# M_H_ext_sound.net
KiCad netlist of a schematic drawn in EAGLE
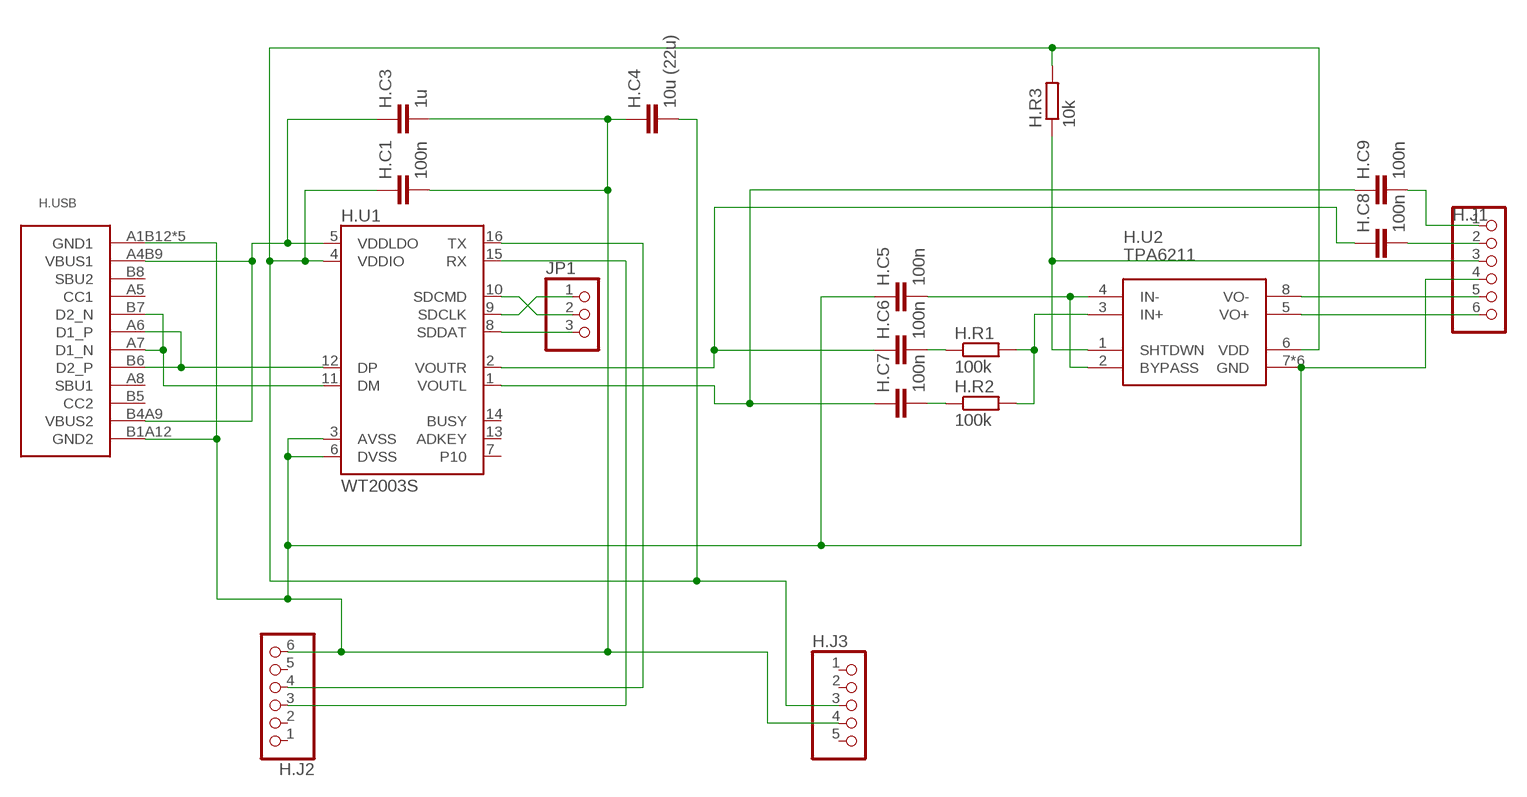
[diagram p0: schematic, sheet 1]

(export (version "E")
  (design (tool "Eeschema 10.0.6"))
  (components
    (comp (ref "H.C1")
      (value "100n")
      (footprint "eagle-import:C0603")
      (libsource (lib "eagle-import") (part "C-EUC0603"))
    )
    (comp (ref "H.C3")
      (value "1u")
      (footprint "eagle-import:C0603")
      (libsource (lib "eagle-import") (part "C-EUC0603"))
    )
    (comp (ref "H.C4")
      (value "10u (22u)")
      (footprint "eagle-import:C0805")
      (libsource (lib "eagle-import") (part "C-EUC0805"))
    )
    (comp (ref "H.C5")
      (value "100n")
      (footprint "eagle-import:C0603")
      (libsource (lib "eagle-import") (part "C-EUC0603"))
    )
    (comp (ref "H.C6")
      (value "100n")
      (footprint "eagle-import:C0603")
      (libsource (lib "eagle-import") (part "C-EUC0603"))
    )
    (comp (ref "H.C7")
      (value "100n")
      (footprint "eagle-import:C0603")
      (libsource (lib "eagle-import") (part "C-EUC0603"))
    )
    (comp (ref "H.C8")
      (value "100n")
      (footprint "eagle-import:C0603")
      (libsource (lib "eagle-import") (part "C-EUC0603"))
    )
    (comp (ref "H.C9")
      (value "100n")
      (footprint "eagle-import:C0603")
      (libsource (lib "eagle-import") (part "C-EUC0603"))
    )
    (comp (ref "H.J1")
      (value "PINHD-1X6")
      (footprint "eagle-import:1X06")
      (libsource (lib "eagle-import") (part "PINHD-1X6"))
    )
    (comp (ref "H.J2")
      (value "PINHD-1X6")
      (footprint "eagle-import:1X06")
      (libsource (lib "eagle-import") (part "PINHD-1X6"))
    )
    (comp (ref "H.J3")
      (value "PINHD-1X5")
      (footprint "eagle-import:1X05")
      (libsource (lib "eagle-import") (part "PINHD-1X5"))
    )
    (comp (ref "H.R1")
      (value "100k")
      (footprint "eagle-import:R0603")
      (libsource (lib "eagle-import") (part "R-EU_R0603"))
    )
    (comp (ref "H.R2")
      (value "100k")
      (footprint "eagle-import:R0603")
      (libsource (lib "eagle-import") (part "R-EU_R0603"))
    )
    (comp (ref "H.R3")
      (value "10k")
      (footprint "eagle-import:R0603")
      (libsource (lib "eagle-import") (part "R-EU_R0603"))
    )
    (comp (ref "H.U1")
      (value "WT2003S")
      (footprint "eagle-import:SO16")
      (libsource (lib "eagle-import") (part "WT2003S"))
    )
    (comp (ref "H.U2")
      (value "TPA6211")
      (footprint "eagle-import:MSOP-POWERPAD-8")
      (libsource (lib "eagle-import") (part "TPA6211"))
    )
    (comp (ref "H.USB")
      (value "USB-C")
      (footprint "eagle-import:USB-C")
      (libsource (lib "eagle-import") (part "USB-C"))
    )
    (comp (ref "JP1")
      (value "PINHD-1X3")
      (footprint "eagle-import:1X03")
      (libsource (lib "eagle-import") (part "PINHD-1X3"))
    )
  )
  (nets
    (net (code "1") (name "Net-(H.C6-Pad2)") (class "Default")
      (node (ref "H.C6") (pin "2") (pinfunction "2_2") (pintype "passive"))
      (node (ref "H.R1") (pin "1") (pinfunction "1_1") (pintype "passive"))
    )
    (net (code "2") (name "Net-(H.C7-Pad2)") (class "Default")
      (node (ref "H.C7") (pin "2") (pinfunction "2_2") (pintype "passive"))
      (node (ref "H.R2") (pin "1") (pinfunction "1_1") (pintype "passive"))
    )
    (net (code "3") (name "Net-(H.C8-Pad2)") (class "Default")
      (node (ref "H.C8") (pin "2") (pinfunction "2_2") (pintype "passive"))
      (node (ref "H.J1") (pin "2") (pinfunction "2_2") (pintype "passive"))
    )
    (net (code "4") (name "Net-(H.C9-Pad2)") (class "Default")
      (node (ref "H.C9") (pin "2") (pinfunction "2_2") (pintype "passive"))
      (node (ref "H.J1") (pin "1") (pinfunction "1_1") (pintype "passive"))
    )
    (net (code "5") (name "Net-(H.U1-AVSS)") (class "Default")
      (node (ref "H.C1") (pin "2") (pinfunction "2_2") (pintype "passive"))
      (node (ref "H.C3") (pin "2") (pinfunction "2_2") (pintype "passive"))
      (node (ref "H.C4") (pin "1") (pinfunction "1_1") (pintype "passive"))
      (node (ref "H.C5") (pin "1") (pinfunction "1_1") (pintype "passive"))
      (node (ref "H.J1") (pin "4") (pinfunction "4_4") (pintype "passive"))
      (node (ref "H.J2") (pin "6") (pinfunction "6_6") (pintype "passive"))
      (node (ref "H.J3") (pin "4") (pinfunction "4_4") (pintype "passive"))
      (node (ref "H.U1") (pin "3") (pinfunction "AVSS_3") (pintype "bidirectional"))
      (node (ref "H.U1") (pin "6") (pinfunction "DVSS_6") (pintype "bidirectional"))
      (node (ref "H.U2") (pin "7") (pinfunction "GND_7") (pintype "bidirectional"))
      (node (ref "H.U2") (pin "9") (pinfunction "GND_9") (pintype "bidirectional"))
      (node (ref "H.U2") (pin "P$10") (pinfunction "GND_P$10") (pintype "bidirectional"))
      (node (ref "H.U2") (pin "P$11") (pinfunction "GND_P$11") (pintype "bidirectional"))
      (node (ref "H.U2") (pin "P$12") (pinfunction "GND_P$12") (pintype "bidirectional"))
      (node (ref "H.U2") (pin "P$13") (pinfunction "GND_P$13") (pintype "bidirectional"))
      (node (ref "H.USB") (pin "A1B12") (pinfunction "GND1_A1B12") (pintype "bidirectional"))
      (node (ref "H.USB") (pin "B1A12") (pinfunction "GND2_B1A12") (pintype "bidirectional"))
      (node (ref "H.USB") (pin "SH1") (pinfunction "GND1_SH1") (pintype "bidirectional"))
      (node (ref "H.USB") (pin "SH2") (pinfunction "GND1_SH2") (pintype "bidirectional"))
      (node (ref "H.USB") (pin "SH3") (pinfunction "GND1_SH3") (pintype "bidirectional"))
      (node (ref "H.USB") (pin "SH4") (pinfunction "GND1_SH4") (pintype "bidirectional"))
    )
    (net (code "6") (name "Net-(H.U1-DM)") (class "Default")
      (node (ref "H.U1") (pin "11") (pinfunction "DM_11") (pintype "bidirectional"))
      (node (ref "H.USB") (pin "A7") (pinfunction "D1_N_A7") (pintype "bidirectional"))
      (node (ref "H.USB") (pin "B7") (pinfunction "D2_N_B7") (pintype "bidirectional"))
    )
    (net (code "7") (name "Net-(H.U1-DP)") (class "Default")
      (node (ref "H.U1") (pin "12") (pinfunction "DP_12") (pintype "bidirectional"))
      (node (ref "H.USB") (pin "A6") (pinfunction "D1_P_A6") (pintype "bidirectional"))
      (node (ref "H.USB") (pin "B6") (pinfunction "D2_P_B6") (pintype "bidirectional"))
    )
    (net (code "8") (name "Net-(H.U1-RX)") (class "Default")
      (node (ref "H.J2") (pin "3") (pinfunction "3_3") (pintype "passive"))
      (node (ref "H.U1") (pin "15") (pinfunction "RX_15") (pintype "bidirectional"))
    )
    (net (code "9") (name "Net-(H.U1-SDCLK)") (class "Default")
      (node (ref "H.U1") (pin "9") (pinfunction "SDCLK_9") (pintype "bidirectional"))
      (node (ref "JP1") (pin "1") (pinfunction "1_1") (pintype "passive"))
    )
    (net (code "10") (name "Net-(H.U1-SDCMD)") (class "Default")
      (node (ref "H.U1") (pin "10") (pinfunction "SDCMD_10") (pintype "bidirectional"))
      (node (ref "JP1") (pin "2") (pinfunction "2_2") (pintype "passive"))
    )
    (net (code "11") (name "Net-(H.U1-SDDAT)") (class "Default")
      (node (ref "H.U1") (pin "8") (pinfunction "SDDAT_8") (pintype "bidirectional"))
      (node (ref "JP1") (pin "3") (pinfunction "3_3") (pintype "passive"))
    )
    (net (code "12") (name "Net-(H.U1-TX)") (class "Default")
      (node (ref "H.J2") (pin "4") (pinfunction "4_4") (pintype "passive"))
      (node (ref "H.U1") (pin "16") (pinfunction "TX_16") (pintype "bidirectional"))
    )
    (net (code "13") (name "Net-(H.U1-VDDIO)") (class "Default")
      (node (ref "H.C1") (pin "1") (pinfunction "1_1") (pintype "passive"))
      (node (ref "H.C4") (pin "2") (pinfunction "2_2") (pintype "passive"))
      (node (ref "H.J3") (pin "3") (pinfunction "3_3") (pintype "passive"))
      (node (ref "H.R3") (pin "2") (pinfunction "2_2") (pintype "passive"))
      (node (ref "H.U1") (pin "4") (pinfunction "VDDIO_4") (pintype "bidirectional"))
      (node (ref "H.U2") (pin "6") (pinfunction "VDD_6") (pintype "bidirectional"))
    )
    (net (code "14") (name "Net-(H.U1-VDDLDO)") (class "Default")
      (node (ref "H.C3") (pin "1") (pinfunction "1_1") (pintype "passive"))
      (node (ref "H.U1") (pin "5") (pinfunction "VDDLDO_5") (pintype "bidirectional"))
      (node (ref "H.USB") (pin "A4B9") (pinfunction "VBUS1_A4B9") (pintype "bidirectional"))
      (node (ref "H.USB") (pin "B4A9") (pinfunction "VBUS2_B4A9") (pintype "bidirectional"))
    )
    (net (code "15") (name "Net-(H.U1-VOUTL)") (class "Default")
      (node (ref "H.C7") (pin "1") (pinfunction "1_1") (pintype "passive"))
      (node (ref "H.C9") (pin "1") (pinfunction "1_1") (pintype "passive"))
      (node (ref "H.U1") (pin "1") (pinfunction "VOUTL_1") (pintype "bidirectional"))
    )
    (net (code "16") (name "Net-(H.U1-VOUTR)") (class "Default")
      (node (ref "H.C6") (pin "1") (pinfunction "1_1") (pintype "passive"))
      (node (ref "H.C8") (pin "1") (pinfunction "1_1") (pintype "passive"))
      (node (ref "H.U1") (pin "2") (pinfunction "VOUTR_2") (pintype "bidirectional"))
    )
    (net (code "17") (name "Net-(H.U2-BYPASS)") (class "Default")
      (node (ref "H.C5") (pin "2") (pinfunction "2_2") (pintype "passive"))
      (node (ref "H.U2") (pin "2") (pinfunction "BYPASS_2") (pintype "bidirectional"))
      (node (ref "H.U2") (pin "4") (pinfunction "IN-_4") (pintype "bidirectional"))
    )
    (net (code "18") (name "Net-(H.U2-IN+)") (class "Default")
      (node (ref "H.R1") (pin "2") (pinfunction "2_2") (pintype "passive"))
      (node (ref "H.R2") (pin "2") (pinfunction "2_2") (pintype "passive"))
      (node (ref "H.U2") (pin "3") (pinfunction "IN+_3") (pintype "bidirectional"))
    )
    (net (code "19") (name "Net-(H.U2-SHTDWN)") (class "Default")
      (node (ref "H.J1") (pin "3") (pinfunction "3_3") (pintype "passive"))
      (node (ref "H.R3") (pin "1") (pinfunction "1_1") (pintype "passive"))
      (node (ref "H.U2") (pin "1") (pinfunction "SHTDWN_1") (pintype "bidirectional"))
    )
    (net (code "20") (name "Net-(H.U2-VO+)") (class "Default")
      (node (ref "H.J1") (pin "6") (pinfunction "6_6") (pintype "passive"))
      (node (ref "H.U2") (pin "5") (pinfunction "VO+_5") (pintype "bidirectional"))
    )
    (net (code "21") (name "Net-(H.U2-VO-)") (class "Default")
      (node (ref "H.J1") (pin "5") (pinfunction "5_5") (pintype "passive"))
      (node (ref "H.U2") (pin "8") (pinfunction "VO-_8") (pintype "bidirectional"))
    )
    (net (code "22") (name "unconnected-(H.J2-Pad1)") (class "Default")
      (node (ref "H.J2") (pin "1") (pinfunction "1_1") (pintype "passive"))
    )
    (net (code "23") (name "unconnected-(H.J2-Pad2)") (class "Default")
      (node (ref "H.J2") (pin "2") (pinfunction "2_2") (pintype "passive"))
    )
    (net (code "24") (name "unconnected-(H.J2-Pad5)") (class "Default")
      (node (ref "H.J2") (pin "5") (pinfunction "5_5") (pintype "passive"))
    )
    (net (code "25") (name "unconnected-(H.J3-Pad1)") (class "Default")
      (node (ref "H.J3") (pin "1") (pinfunction "1_1") (pintype "passive"))
    )
    (net (code "26") (name "unconnected-(H.J3-Pad2)") (class "Default")
      (node (ref "H.J3") (pin "2") (pinfunction "2_2") (pintype "passive"))
    )
    (net (code "27") (name "unconnected-(H.J3-Pad5)") (class "Default")
      (node (ref "H.J3") (pin "5") (pinfunction "5_5") (pintype "passive"))
    )
    (net (code "28") (name "unconnected-(H.U1-ADKEY-Pad13)") (class "Default")
      (node (ref "H.U1") (pin "13") (pinfunction "ADKEY_13") (pintype "bidirectional"))
    )
    (net (code "29") (name "unconnected-(H.U1-BUSY-Pad14)") (class "Default")
      (node (ref "H.U1") (pin "14") (pinfunction "BUSY_14") (pintype "bidirectional"))
    )
    (net (code "30") (name "unconnected-(H.U1-P10-Pad7)") (class "Default")
      (node (ref "H.U1") (pin "7") (pinfunction "P10_7") (pintype "bidirectional"))
    )
    (net (code "31") (name "unconnected-(H.USB-CC1-PadA5)") (class "Default")
      (node (ref "H.USB") (pin "A5") (pinfunction "CC1_A5") (pintype "bidirectional"))
    )
    (net (code "32") (name "unconnected-(H.USB-CC2-PadB5)") (class "Default")
      (node (ref "H.USB") (pin "B5") (pinfunction "CC2_B5") (pintype "bidirectional"))
    )
    (net (code "33") (name "unconnected-(H.USB-SBU1-PadA8)") (class "Default")
      (node (ref "H.USB") (pin "A8") (pinfunction "SBU1_A8") (pintype "bidirectional"))
    )
    (net (code "34") (name "unconnected-(H.USB-SBU2-PadB8)") (class "Default")
      (node (ref "H.USB") (pin "B8") (pinfunction "SBU2_B8") (pintype "bidirectional"))
    )
  )
)
